# Thermistor_Channel.net
KiCad netlist of a schematic drawn in Altium Designer
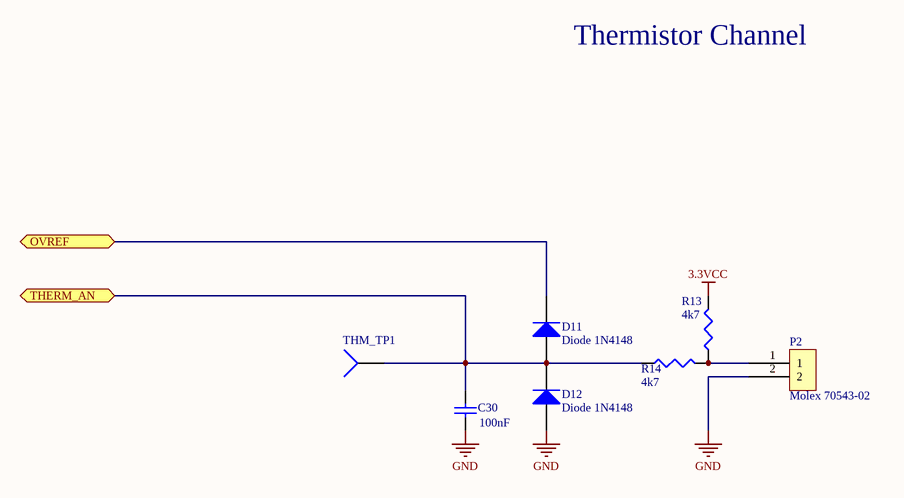
[diagram p0: Thermistor Channel.SchDoc]

(export (version "E")
  (design (tool "Eeschema 10.0.6"))
  (components
    (comp (ref "C30")
      (value "100nF")
      (footprint "1608[0603]")
      (description "Capacitor (Semiconductor SIM Model)")
      (fields (field (name "Comment") "Cap Semi") (field (name "PUBLISHER") "Altium Limited"))
      (libsource (lib "Miscellaneous Devices") (part "Cap Semi"))
    )
    (comp (ref "D11")
      (value "Diode 1N4148")
      (footprint "1N4148WT")
      (description "High Conductance Fast Diode")
      (fields (field (name "PUBLISHER") "Altium Limited"))
      (libsource (lib "Miscellaneous Devices") (part "Diode 1N4148"))
    )
    (comp (ref "D12")
      (value "Diode 1N4148")
      (footprint "1N4148WT")
      (description "High Conductance Fast Diode")
      (fields (field (name "PUBLISHER") "Altium Limited"))
      (libsource (lib "Miscellaneous Devices") (part "Diode 1N4148"))
    )
    (comp (ref "P2")
      (value "Molex 70543-02")
      (footprint "70543-02")
      (libsource (lib "ZMBo Schematic Library") (part "Molex 70543-02"))
    )
    (comp (ref "R13")
      (value "4k7")
      (footprint "J1-0603")
      (description "Resistor")
      (fields (field (name "Comment") "Res3") (field (name "PUBLISHER") "Altium Limited"))
      (libsource (lib "Miscellaneous Devices") (part "Res3"))
    )
    (comp (ref "R14")
      (value "4k7")
      (footprint "J1-0603")
      (description "Resistor")
      (fields (field (name "Comment") "Res3") (field (name "PUBLISHER") "Altium Limited"))
      (libsource (lib "Miscellaneous Devices") (part "Res3"))
    )
    (comp (ref "THM_TP1")
      (value "TP4")
      (footprint "PIN1")
      (description "Socket")
      (fields (field (name "PUBLISHER") "Altium Limited"))
      (libsource (lib "Miscellaneous Connectors") (part "Socket"))
    )
  )
  (nets
    (net (code "1") (name "/OVREF") (class "Default")
      (node (ref "D11") (pin "2") (pinfunction "K_2") (pintype "passive"))
    )
    (net (code "2") (name "/THERM_AN") (class "Default")
      (node (ref "C30") (pin "2") (pinfunction "2_2") (pintype "passive"))
      (node (ref "D11") (pin "1") (pinfunction "A_1") (pintype "passive"))
      (node (ref "D12") (pin "2") (pinfunction "K_2") (pintype "passive"))
      (node (ref "R14") (pin "1") (pinfunction "1_1") (pintype "passive"))
      (node (ref "THM_TP1") (pin "1") (pinfunction "1_1") (pintype "passive"))
    )
    (net (code "3") (name "3.3VCC") (class "Default")
      (node (ref "R13") (pin "2") (pinfunction "2_2") (pintype "passive"))
    )
    (net (code "4") (name "GND") (class "Default")
      (node (ref "C30") (pin "1") (pinfunction "1_1") (pintype "passive"))
      (node (ref "D12") (pin "1") (pinfunction "A_1") (pintype "passive"))
      (node (ref "P2") (pin "2") (pinfunction "2_2") (pintype "passive"))
    )
    (net (code "5") (name "Net-(P2-Pad1)") (class "Default")
      (node (ref "P2") (pin "1") (pinfunction "1_1") (pintype "passive"))
      (node (ref "R13") (pin "1") (pinfunction "1_1") (pintype "passive"))
      (node (ref "R14") (pin "2") (pinfunction "2_2") (pintype "passive"))
    )
  )
)
